# CTR-Lower-Main-Board-Rev-C-LED-5.net
KiCad netlist of a schematic drawn in Altium Designer
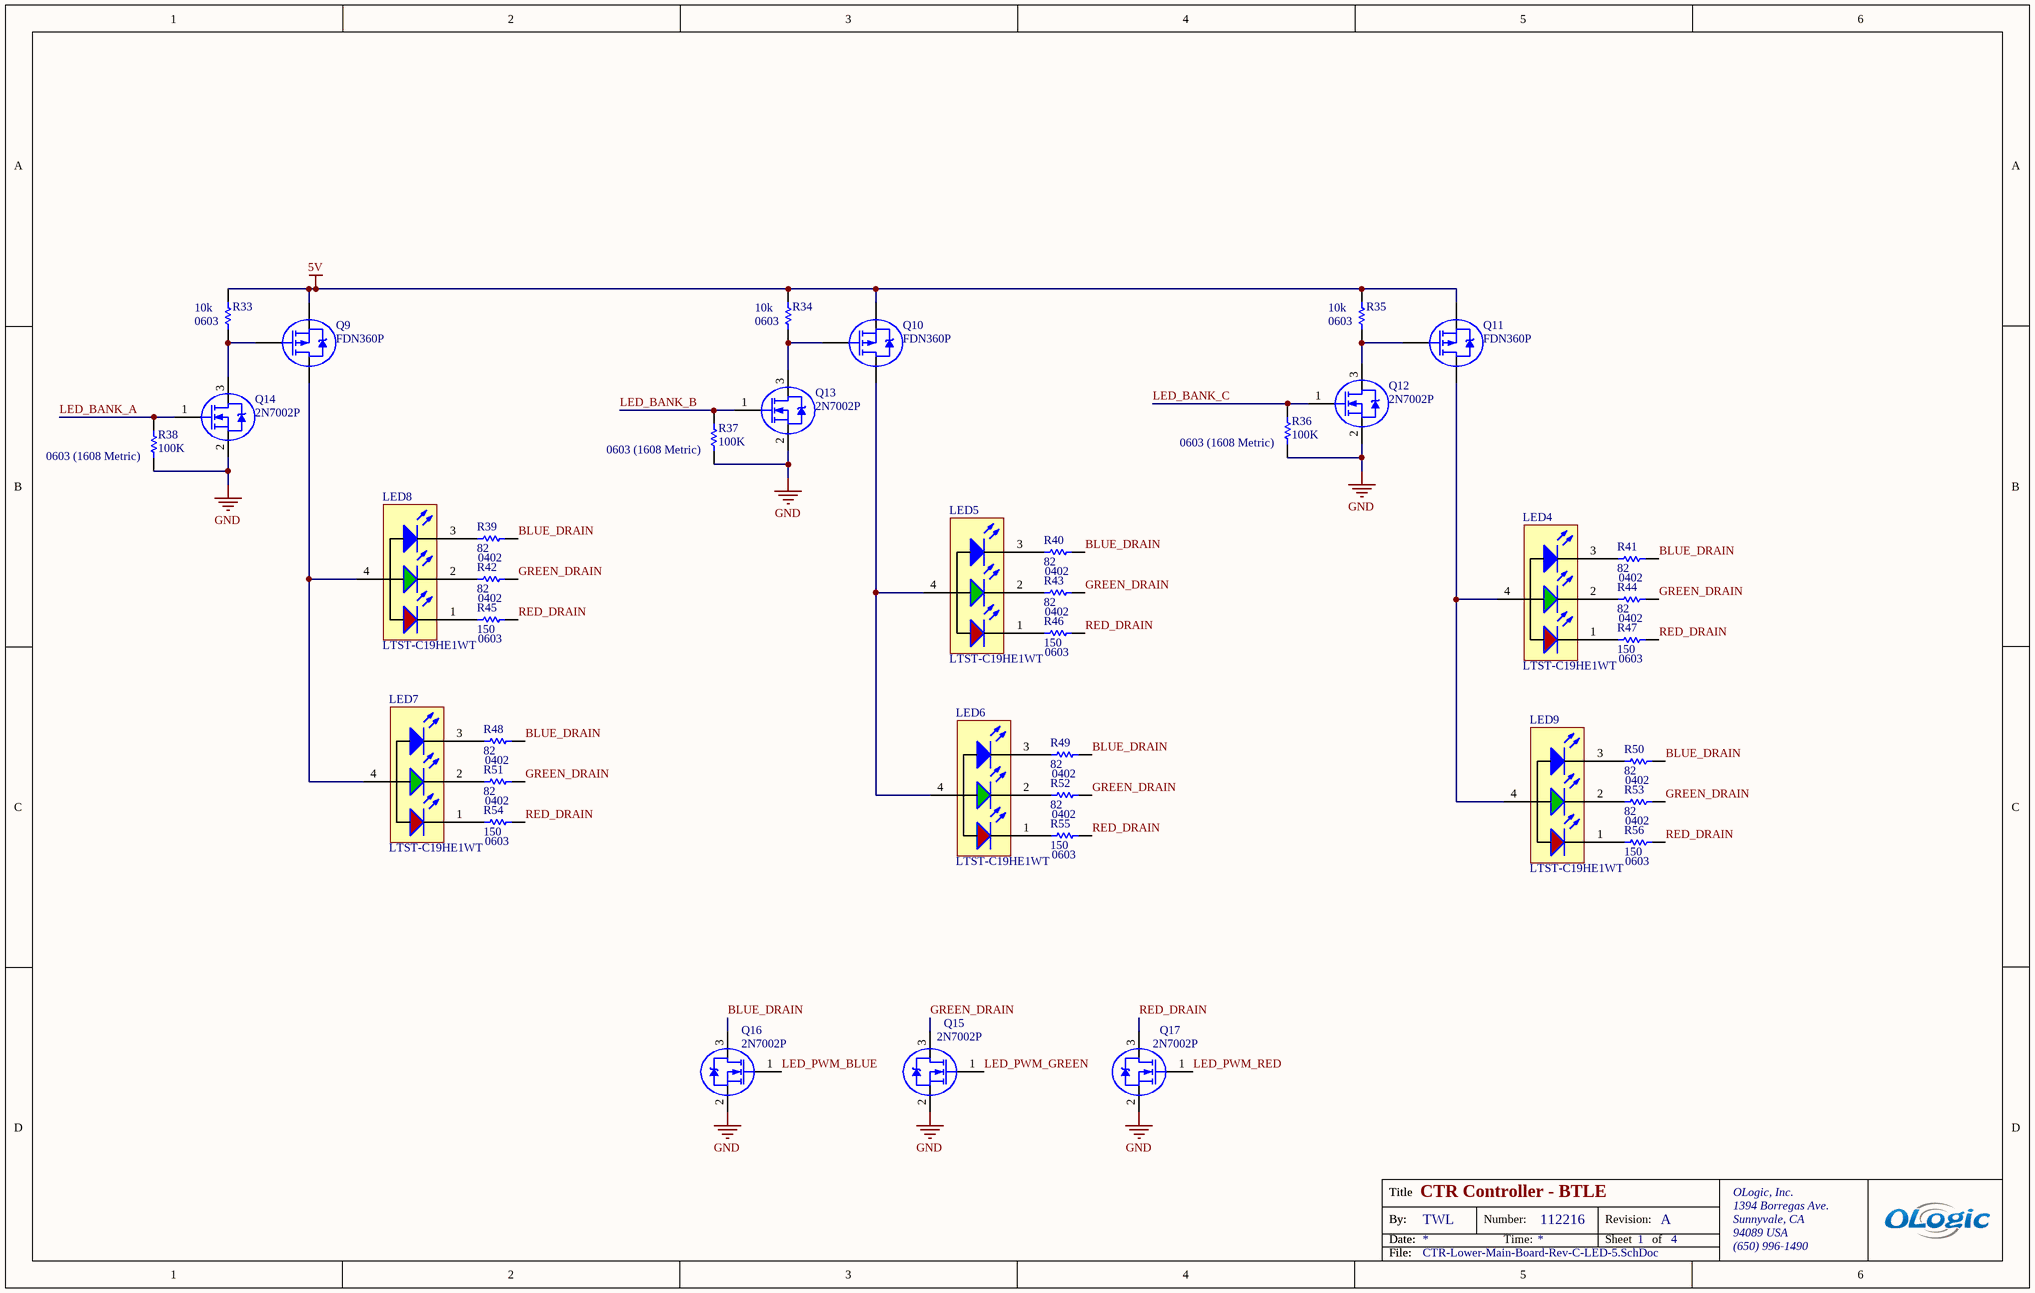
[diagram p0: CTR-Lower-Main-Board-Rev-C-LED-5.SchDoc]

(export (version "E")
  (design (tool "Eeschema 10.0.6"))
  (components
    (comp (ref "LED4")
      (value "Red, Green, Blue (RGB)")
      (footprint "LTST-C19HE1WT")
      (description "LED RGB 624/525/470NM DIFF SMD")
      (fields
        (field (name "MANUFACTURER") "Lite-On Inc.")
        (field (name "MANUFACTURER PART NUMBER") "LTST-C19HE1WT")
      )
      (libsource (lib "OLogic-Diode-Opto-LED") (part "LTST-C19HE1WT"))
    )
    (comp (ref "LED5")
      (value "Red, Green, Blue (RGB)")
      (footprint "LTST-C19HE1WT")
      (description "LED RGB 624/525/470NM DIFF SMD")
      (fields
        (field (name "MANUFACTURER") "Lite-On Inc.")
        (field (name "MANUFACTURER PART NUMBER") "LTST-C19HE1WT")
      )
      (libsource (lib "OLogic-Diode-Opto-LED") (part "LTST-C19HE1WT"))
    )
    (comp (ref "LED6")
      (value "Red, Green, Blue (RGB)")
      (footprint "LTST-C19HE1WT")
      (description "LED RGB 624/525/470NM DIFF SMD")
      (fields
        (field (name "MANUFACTURER") "Lite-On Inc.")
        (field (name "MANUFACTURER PART NUMBER") "LTST-C19HE1WT")
      )
      (libsource (lib "OLogic-Diode-Opto-LED") (part "LTST-C19HE1WT"))
    )
    (comp (ref "LED7")
      (value "Red, Green, Blue (RGB)")
      (footprint "LTST-C19HE1WT")
      (description "LED RGB 624/525/470NM DIFF SMD")
      (fields
        (field (name "MANUFACTURER") "Lite-On Inc.")
        (field (name "MANUFACTURER PART NUMBER") "LTST-C19HE1WT")
      )
      (libsource (lib "OLogic-Diode-Opto-LED") (part "LTST-C19HE1WT"))
    )
    (comp (ref "LED8")
      (value "Red, Green, Blue (RGB)")
      (footprint "LTST-C19HE1WT")
      (description "LED RGB 624/525/470NM DIFF SMD")
      (fields
        (field (name "MANUFACTURER") "Lite-On Inc.")
        (field (name "MANUFACTURER PART NUMBER") "LTST-C19HE1WT")
      )
      (libsource (lib "OLogic-Diode-Opto-LED") (part "LTST-C19HE1WT"))
    )
    (comp (ref "LED9")
      (value "Red, Green, Blue (RGB)")
      (footprint "LTST-C19HE1WT")
      (description "LED RGB 624/525/470NM DIFF SMD")
      (fields
        (field (name "MANUFACTURER") "Lite-On Inc.")
        (field (name "MANUFACTURER PART NUMBER") "LTST-C19HE1WT")
      )
      (libsource (lib "OLogic-Diode-Opto-LED") (part "LTST-C19HE1WT"))
    )
    (comp (ref "Q9")
      (value "FDN360P")
      (footprint "SOT23")
      (description "Single P-Channel MOSFET")
      (fields (field (name "MANUFACTURER") "Fairchild Semi"))
      (libsource (lib "OLogic-Trans-Drivers") (part "FDN360P"))
    )
    (comp (ref "Q10")
      (value "FDN360P")
      (footprint "SOT23")
      (description "Single P-Channel MOSFET")
      (fields (field (name "MANUFACTURER") "Fairchild Semi"))
      (libsource (lib "OLogic-Trans-Drivers") (part "FDN360P"))
    )
    (comp (ref "Q11")
      (value "FDN360P")
      (footprint "SOT23")
      (description "Single P-Channel MOSFET")
      (fields (field (name "MANUFACTURER") "Fairchild Semi"))
      (libsource (lib "OLogic-Trans-Drivers") (part "FDN360P"))
    )
    (comp (ref "Q12")
      (value "2N7002P")
      (footprint "SOT23")
      (description "MOSFET N-CH 60V 0.36A SOT-23")
      (fields
        (field (name "MANUFACTURER") "NXP Semiconductors")
        (field (name "MANUFACTURER PART NUMBER") "2N7002P,235")
      )
      (libsource (lib "OLogic-Trans-Drivers") (part "2N7002P"))
    )
    (comp (ref "Q13")
      (value "2N7002P")
      (footprint "SOT23")
      (description "MOSFET N-CH 60V 0.36A SOT-23")
      (fields
        (field (name "MANUFACTURER") "NXP Semiconductors")
        (field (name "MANUFACTURER PART NUMBER") "2N7002P,235")
      )
      (libsource (lib "OLogic-Trans-Drivers") (part "2N7002P"))
    )
    (comp (ref "Q14")
      (value "2N7002P")
      (footprint "SOT23")
      (description "MOSFET N-CH 60V 0.36A SOT-23")
      (fields
        (field (name "MANUFACTURER") "NXP Semiconductors")
        (field (name "MANUFACTURER PART NUMBER") "2N7002P,235")
      )
      (libsource (lib "OLogic-Trans-Drivers") (part "2N7002P"))
    )
    (comp (ref "Q15")
      (value "2N7002P")
      (footprint "SOT23")
      (description "MOSFET N-CH 60V 0.36A SOT-23")
      (fields
        (field (name "MANUFACTURER") "NXP Semiconductors")
        (field (name "MANUFACTURER PART NUMBER") "2N7002P,235")
      )
      (libsource (lib "") (part "2N7002P_1"))
    )
    (comp (ref "Q16")
      (value "2N7002P")
      (footprint "SOT23")
      (description "MOSFET N-CH 60V 0.36A SOT-23")
      (fields
        (field (name "MANUFACTURER") "NXP Semiconductors")
        (field (name "MANUFACTURER PART NUMBER") "2N7002P,235")
      )
      (libsource (lib "") (part "2N7002P_1"))
    )
    (comp (ref "Q17")
      (value "2N7002P")
      (footprint "SOT23")
      (description "MOSFET N-CH 60V 0.36A SOT-23")
      (fields
        (field (name "MANUFACTURER") "NXP Semiconductors")
        (field (name "MANUFACTURER PART NUMBER") "2N7002P,235")
      )
      (libsource (lib "") (part "2N7002P_1"))
    )
    (comp (ref "R33")
      (value "10K 1%")
      (footprint "RESC0603(1608)_N")
      (description "10K 0603")
      (fields
        (field (name "MANUFACTURER") "Panasonic Electronic Components")
        (field (name "MANUFACTURER PART NUMBER") "ERJ-3EKF1002V")
        (field (name "RESISTANCE (OHMS)") "10k")
        (field (name "SUPPLIER DEVICE PACKAGE") "0603")
      )
      (libsource (lib "OLogic-Passive") (part "RES 10K OHM 1/10W 1% 0603 SMD"))
    )
    (comp (ref "R34")
      (value "10K 1%")
      (footprint "RESC0603(1608)_N")
      (description "10K 0603")
      (fields
        (field (name "MANUFACTURER") "Panasonic Electronic Components")
        (field (name "MANUFACTURER PART NUMBER") "ERJ-3EKF1002V")
        (field (name "RESISTANCE (OHMS)") "10k")
        (field (name "SUPPLIER DEVICE PACKAGE") "0603")
      )
      (libsource (lib "OLogic-Passive") (part "RES 10K OHM 1/10W 1% 0603 SMD"))
    )
    (comp (ref "R35")
      (value "10K 1%")
      (footprint "RESC0603(1608)_N")
      (description "10K 0603")
      (fields
        (field (name "MANUFACTURER") "Panasonic Electronic Components")
        (field (name "MANUFACTURER PART NUMBER") "ERJ-3EKF1002V")
        (field (name "RESISTANCE (OHMS)") "10k")
        (field (name "SUPPLIER DEVICE PACKAGE") "0603")
      )
      (libsource (lib "OLogic-Passive") (part "RES 10K OHM 1/10W 1% 0603 SMD"))
    )
    (comp (ref "R36")
      (value "100K")
      (footprint "RESC0603(1608)_N")
      (description "100K 0603")
      (fields
        (field (name "MANUFACTURER") "Rohm Semiconductor")
        (field (name "MANUFACTURER PART NUMBER") "ESR03EZPJ104")
        (field (name "PACKAGE / CASE") "0603 (1608 Metric)")
      )
      (libsource (lib "OLogic-Passive") (part "RES 100K OHM 5% 1/4W 0603"))
    )
    (comp (ref "R37")
      (value "100K")
      (footprint "RESC0603(1608)_N")
      (description "100K 0603")
      (fields
        (field (name "MANUFACTURER") "Rohm Semiconductor")
        (field (name "MANUFACTURER PART NUMBER") "ESR03EZPJ104")
        (field (name "PACKAGE / CASE") "0603 (1608 Metric)")
      )
      (libsource (lib "OLogic-Passive") (part "RES 100K OHM 5% 1/4W 0603"))
    )
    (comp (ref "R38")
      (value "100K")
      (footprint "RESC0603(1608)_N")
      (description "100K 0603")
      (fields
        (field (name "MANUFACTURER") "Rohm Semiconductor")
        (field (name "MANUFACTURER PART NUMBER") "ESR03EZPJ104")
        (field (name "PACKAGE / CASE") "0603 (1608 Metric)")
      )
      (libsource (lib "OLogic-Passive") (part "RES 100K OHM 5% 1/4W 0603"))
    )
    (comp (ref "R39")
      (value "?")
      (footprint "RESC0402(1005)_N")
      (description "82 0402")
      (fields
        (field (name "MANUFACTURER") "Panasonic Electronic Components")
        (field (name "MANUFACTURER PART NUMBER") "ERJ-2RKF82R0X")
        (field (name "SUPPLIER DEVICE PACKAGE") "0402")
        (field (name "RESISTANCE (OHMS)") "82")
        (field (name "CREATOR") "osman")
      )
      (libsource (lib "OLogic-Passive") (part "RES 82 OHM 1% 1/10W 0402"))
    )
    (comp (ref "R40")
      (value "?")
      (footprint "RESC0402(1005)_N")
      (description "82 0402")
      (fields
        (field (name "MANUFACTURER") "Panasonic Electronic Components")
        (field (name "MANUFACTURER PART NUMBER") "ERJ-2RKF82R0X")
        (field (name "SUPPLIER DEVICE PACKAGE") "0402")
        (field (name "RESISTANCE (OHMS)") "82")
        (field (name "CREATOR") "osman")
      )
      (libsource (lib "OLogic-Passive") (part "RES 82 OHM 1% 1/10W 0402"))
    )
    (comp (ref "R41")
      (value "?")
      (footprint "RESC0402(1005)_N")
      (description "82 0402")
      (fields
        (field (name "MANUFACTURER") "Panasonic Electronic Components")
        (field (name "MANUFACTURER PART NUMBER") "ERJ-2RKF82R0X")
        (field (name "SUPPLIER DEVICE PACKAGE") "0402")
        (field (name "RESISTANCE (OHMS)") "82")
        (field (name "CREATOR") "osman")
      )
      (libsource (lib "OLogic-Passive") (part "RES 82 OHM 1% 1/10W 0402"))
    )
    (comp (ref "R42")
      (value "?")
      (footprint "RESC0402(1005)_N")
      (description "82 0402")
      (fields
        (field (name "MANUFACTURER") "Panasonic Electronic Components")
        (field (name "MANUFACTURER PART NUMBER") "ERJ-2RKF82R0X")
        (field (name "SUPPLIER DEVICE PACKAGE") "0402")
        (field (name "RESISTANCE (OHMS)") "82")
        (field (name "CREATOR") "osman")
      )
      (libsource (lib "OLogic-Passive") (part "RES 82 OHM 1% 1/10W 0402"))
    )
    (comp (ref "R43")
      (value "?")
      (footprint "RESC0402(1005)_N")
      (description "82 0402")
      (fields
        (field (name "MANUFACTURER") "Panasonic Electronic Components")
        (field (name "MANUFACTURER PART NUMBER") "ERJ-2RKF82R0X")
        (field (name "SUPPLIER DEVICE PACKAGE") "0402")
        (field (name "RESISTANCE (OHMS)") "82")
        (field (name "CREATOR") "osman")
      )
      (libsource (lib "OLogic-Passive") (part "RES 82 OHM 1% 1/10W 0402"))
    )
    (comp (ref "R44")
      (value "?")
      (footprint "RESC0402(1005)_N")
      (description "82 0402")
      (fields
        (field (name "MANUFACTURER") "Panasonic Electronic Components")
        (field (name "MANUFACTURER PART NUMBER") "ERJ-2RKF82R0X")
        (field (name "SUPPLIER DEVICE PACKAGE") "0402")
        (field (name "RESISTANCE (OHMS)") "82")
        (field (name "CREATOR") "osman")
      )
      (libsource (lib "OLogic-Passive") (part "RES 82 OHM 1% 1/10W 0402"))
    )
    (comp (ref "R45")
      (value "150")
      (footprint "RESC0603(1608)_N")
      (description "150 0603")
      (fields
        (field (name "MANUFACTURER") "Yageo")
        (field (name "MANUFACTURER PART NUMBER") "RC0603FR-07150RL")
        (field (name "SUPPLIER DEVICE PACKAGE") "0603")
      )
      (libsource (lib "OLogic-Passive") (part "RES 150 OHM 1/10W 1% 0603 SMD"))
    )
    (comp (ref "R46")
      (value "150")
      (footprint "RESC0603(1608)_N")
      (description "150 0603")
      (fields
        (field (name "MANUFACTURER") "Yageo")
        (field (name "MANUFACTURER PART NUMBER") "RC0603FR-07150RL")
        (field (name "SUPPLIER DEVICE PACKAGE") "0603")
      )
      (libsource (lib "OLogic-Passive") (part "RES 150 OHM 1/10W 1% 0603 SMD"))
    )
    (comp (ref "R47")
      (value "150")
      (footprint "RESC0603(1608)_N")
      (description "150 0603")
      (fields
        (field (name "MANUFACTURER") "Yageo")
        (field (name "MANUFACTURER PART NUMBER") "RC0603FR-07150RL")
        (field (name "SUPPLIER DEVICE PACKAGE") "0603")
      )
      (libsource (lib "OLogic-Passive") (part "RES 150 OHM 1/10W 1% 0603 SMD"))
    )
    (comp (ref "R48")
      (value "?")
      (footprint "RESC0402(1005)_N")
      (description "82 0402")
      (fields
        (field (name "MANUFACTURER") "Panasonic Electronic Components")
        (field (name "MANUFACTURER PART NUMBER") "ERJ-2RKF82R0X")
        (field (name "SUPPLIER DEVICE PACKAGE") "0402")
        (field (name "RESISTANCE (OHMS)") "82")
        (field (name "CREATOR") "osman")
      )
      (libsource (lib "OLogic-Passive") (part "RES 82 OHM 1% 1/10W 0402"))
    )
    (comp (ref "R49")
      (value "?")
      (footprint "RESC0402(1005)_N")
      (description "82 0402")
      (fields
        (field (name "MANUFACTURER") "Panasonic Electronic Components")
        (field (name "MANUFACTURER PART NUMBER") "ERJ-2RKF82R0X")
        (field (name "SUPPLIER DEVICE PACKAGE") "0402")
        (field (name "RESISTANCE (OHMS)") "82")
        (field (name "CREATOR") "osman")
      )
      (libsource (lib "OLogic-Passive") (part "RES 82 OHM 1% 1/10W 0402"))
    )
    (comp (ref "R50")
      (value "?")
      (footprint "RESC0402(1005)_N")
      (description "82 0402")
      (fields
        (field (name "MANUFACTURER") "Panasonic Electronic Components")
        (field (name "MANUFACTURER PART NUMBER") "ERJ-2RKF82R0X")
        (field (name "SUPPLIER DEVICE PACKAGE") "0402")
        (field (name "RESISTANCE (OHMS)") "82")
        (field (name "CREATOR") "osman")
      )
      (libsource (lib "OLogic-Passive") (part "RES 82 OHM 1% 1/10W 0402"))
    )
    (comp (ref "R51")
      (value "?")
      (footprint "RESC0402(1005)_N")
      (description "82 0402")
      (fields
        (field (name "MANUFACTURER") "Panasonic Electronic Components")
        (field (name "MANUFACTURER PART NUMBER") "ERJ-2RKF82R0X")
        (field (name "SUPPLIER DEVICE PACKAGE") "0402")
        (field (name "RESISTANCE (OHMS)") "82")
        (field (name "CREATOR") "osman")
      )
      (libsource (lib "OLogic-Passive") (part "RES 82 OHM 1% 1/10W 0402"))
    )
    (comp (ref "R52")
      (value "?")
      (footprint "RESC0402(1005)_N")
      (description "82 0402")
      (fields
        (field (name "MANUFACTURER") "Panasonic Electronic Components")
        (field (name "MANUFACTURER PART NUMBER") "ERJ-2RKF82R0X")
        (field (name "SUPPLIER DEVICE PACKAGE") "0402")
        (field (name "RESISTANCE (OHMS)") "82")
        (field (name "CREATOR") "osman")
      )
      (libsource (lib "OLogic-Passive") (part "RES 82 OHM 1% 1/10W 0402"))
    )
    (comp (ref "R53")
      (value "?")
      (footprint "RESC0402(1005)_N")
      (description "82 0402")
      (fields
        (field (name "MANUFACTURER") "Panasonic Electronic Components")
        (field (name "MANUFACTURER PART NUMBER") "ERJ-2RKF82R0X")
        (field (name "SUPPLIER DEVICE PACKAGE") "0402")
        (field (name "RESISTANCE (OHMS)") "82")
        (field (name "CREATOR") "osman")
      )
      (libsource (lib "OLogic-Passive") (part "RES 82 OHM 1% 1/10W 0402"))
    )
    (comp (ref "R54")
      (value "150")
      (footprint "RESC0603(1608)_N")
      (description "150 0603")
      (fields
        (field (name "MANUFACTURER") "Yageo")
        (field (name "MANUFACTURER PART NUMBER") "RC0603FR-07150RL")
        (field (name "SUPPLIER DEVICE PACKAGE") "0603")
      )
      (libsource (lib "OLogic-Passive") (part "RES 150 OHM 1/10W 1% 0603 SMD"))
    )
    (comp (ref "R55")
      (value "150")
      (footprint "RESC0603(1608)_N")
      (description "150 0603")
      (fields
        (field (name "MANUFACTURER") "Yageo")
        (field (name "MANUFACTURER PART NUMBER") "RC0603FR-07150RL")
        (field (name "SUPPLIER DEVICE PACKAGE") "0603")
      )
      (libsource (lib "OLogic-Passive") (part "RES 150 OHM 1/10W 1% 0603 SMD"))
    )
    (comp (ref "R56")
      (value "150")
      (footprint "RESC0603(1608)_N")
      (description "150 0603")
      (fields
        (field (name "MANUFACTURER") "Yageo")
        (field (name "MANUFACTURER PART NUMBER") "RC0603FR-07150RL")
        (field (name "SUPPLIER DEVICE PACKAGE") "0603")
      )
      (libsource (lib "OLogic-Passive") (part "RES 150 OHM 1/10W 1% 0603 SMD"))
    )
  )
  (nets
    (net (code "1") (name "/BLUE_DRAIN") (class "Default")
      (node (ref "Q16") (pin "3") (pinfunction "D_3") (pintype "power_in"))
      (node (ref "R39") (pin "1") (pinfunction "1_1") (pintype "passive"))
      (node (ref "R40") (pin "1") (pinfunction "1_1") (pintype "passive"))
      (node (ref "R41") (pin "1") (pinfunction "1_1") (pintype "passive"))
      (node (ref "R48") (pin "1") (pinfunction "1_1") (pintype "passive"))
      (node (ref "R49") (pin "1") (pinfunction "1_1") (pintype "passive"))
      (node (ref "R50") (pin "1") (pinfunction "1_1") (pintype "passive"))
    )
    (net (code "2") (name "/GREEN_DRAIN") (class "Default")
      (node (ref "Q15") (pin "3") (pinfunction "D_3") (pintype "power_in"))
      (node (ref "R42") (pin "1") (pinfunction "1_1") (pintype "passive"))
      (node (ref "R43") (pin "1") (pinfunction "1_1") (pintype "passive"))
      (node (ref "R44") (pin "1") (pinfunction "1_1") (pintype "passive"))
      (node (ref "R51") (pin "1") (pinfunction "1_1") (pintype "passive"))
      (node (ref "R52") (pin "1") (pinfunction "1_1") (pintype "passive"))
      (node (ref "R53") (pin "1") (pinfunction "1_1") (pintype "passive"))
    )
    (net (code "3") (name "/LED_BANK_A") (class "Default")
      (node (ref "Q14") (pin "1") (pinfunction "G_1") (pintype "passive"))
      (node (ref "R38") (pin "2") (pinfunction "2_2") (pintype "passive"))
    )
    (net (code "4") (name "/LED_BANK_B") (class "Default")
      (node (ref "Q13") (pin "1") (pinfunction "G_1") (pintype "passive"))
      (node (ref "R37") (pin "2") (pinfunction "2_2") (pintype "passive"))
    )
    (net (code "5") (name "/LED_BANK_C") (class "Default")
      (node (ref "Q12") (pin "1") (pinfunction "G_1") (pintype "passive"))
      (node (ref "R36") (pin "2") (pinfunction "2_2") (pintype "passive"))
    )
    (net (code "6") (name "/LED_PWM_BLUE") (class "Default")
      (node (ref "Q16") (pin "1") (pinfunction "G_1") (pintype "passive"))
    )
    (net (code "7") (name "/LED_PWM_GREEN") (class "Default")
      (node (ref "Q15") (pin "1") (pinfunction "G_1") (pintype "passive"))
    )
    (net (code "8") (name "/LED_PWM_RED") (class "Default")
      (node (ref "Q17") (pin "1") (pinfunction "G_1") (pintype "passive"))
    )
    (net (code "9") (name "/RED_DRAIN") (class "Default")
      (node (ref "Q17") (pin "3") (pinfunction "D_3") (pintype "power_in"))
      (node (ref "R45") (pin "1") (pinfunction "1_1") (pintype "passive"))
      (node (ref "R46") (pin "1") (pinfunction "1_1") (pintype "passive"))
      (node (ref "R47") (pin "1") (pinfunction "1_1") (pintype "passive"))
      (node (ref "R54") (pin "1") (pinfunction "1_1") (pintype "passive"))
      (node (ref "R55") (pin "1") (pinfunction "1_1") (pintype "passive"))
      (node (ref "R56") (pin "1") (pinfunction "1_1") (pintype "passive"))
    )
    (net (code "10") (name "5V") (class "Default")
      (node (ref "Q10") (pin "2") (pinfunction "S_2") (pintype "passive"))
      (node (ref "Q11") (pin "2") (pinfunction "S_2") (pintype "passive"))
      (node (ref "Q9") (pin "2") (pinfunction "S_2") (pintype "passive"))
      (node (ref "R33") (pin "2") (pinfunction "2_2") (pintype "passive"))
      (node (ref "R34") (pin "2") (pinfunction "2_2") (pintype "passive"))
      (node (ref "R35") (pin "2") (pinfunction "2_2") (pintype "passive"))
    )
    (net (code "11") (name "GND") (class "Default")
      (node (ref "Q12") (pin "2") (pinfunction "S_2") (pintype "passive"))
      (node (ref "Q13") (pin "2") (pinfunction "S_2") (pintype "passive"))
      (node (ref "Q14") (pin "2") (pinfunction "S_2") (pintype "passive"))
      (node (ref "Q15") (pin "2") (pinfunction "S_2") (pintype "passive"))
      (node (ref "Q16") (pin "2") (pinfunction "S_2") (pintype "passive"))
      (node (ref "Q17") (pin "2") (pinfunction "S_2") (pintype "passive"))
      (node (ref "R36") (pin "1") (pinfunction "1_1") (pintype "passive"))
      (node (ref "R37") (pin "1") (pinfunction "1_1") (pintype "passive"))
      (node (ref "R38") (pin "1") (pinfunction "1_1") (pintype "passive"))
    )
    (net (code "12") (name "Net-(LED4-Anode)") (class "Default")
      (node (ref "LED4") (pin "4") (pinfunction "Anode_4") (pintype "passive"))
      (node (ref "LED9") (pin "4") (pinfunction "Anode_4") (pintype "passive"))
      (node (ref "Q11") (pin "3") (pinfunction "D_3") (pintype "passive"))
    )
    (net (code "13") (name "Net-(LED4-B)") (class "Default")
      (node (ref "LED4") (pin "3") (pinfunction "B_3") (pintype "passive"))
      (node (ref "R41") (pin "2") (pinfunction "2_2") (pintype "passive"))
    )
    (net (code "14") (name "Net-(LED4-G)") (class "Default")
      (node (ref "LED4") (pin "2") (pinfunction "G_2") (pintype "passive"))
      (node (ref "R44") (pin "2") (pinfunction "2_2") (pintype "passive"))
    )
    (net (code "15") (name "Net-(LED4-R)") (class "Default")
      (node (ref "LED4") (pin "1") (pinfunction "R_1") (pintype "passive"))
      (node (ref "R47") (pin "2") (pinfunction "2_2") (pintype "passive"))
    )
    (net (code "16") (name "Net-(LED5-Anode)") (class "Default")
      (node (ref "LED5") (pin "4") (pinfunction "Anode_4") (pintype "passive"))
      (node (ref "LED6") (pin "4") (pinfunction "Anode_4") (pintype "passive"))
      (node (ref "Q10") (pin "3") (pinfunction "D_3") (pintype "passive"))
    )
    (net (code "17") (name "Net-(LED5-B)") (class "Default")
      (node (ref "LED5") (pin "3") (pinfunction "B_3") (pintype "passive"))
      (node (ref "R40") (pin "2") (pinfunction "2_2") (pintype "passive"))
    )
    (net (code "18") (name "Net-(LED5-G)") (class "Default")
      (node (ref "LED5") (pin "2") (pinfunction "G_2") (pintype "passive"))
      (node (ref "R43") (pin "2") (pinfunction "2_2") (pintype "passive"))
    )
    (net (code "19") (name "Net-(LED5-R)") (class "Default")
      (node (ref "LED5") (pin "1") (pinfunction "R_1") (pintype "passive"))
      (node (ref "R46") (pin "2") (pinfunction "2_2") (pintype "passive"))
    )
    (net (code "20") (name "Net-(LED6-B)") (class "Default")
      (node (ref "LED6") (pin "3") (pinfunction "B_3") (pintype "passive"))
      (node (ref "R49") (pin "2") (pinfunction "2_2") (pintype "passive"))
    )
    (net (code "21") (name "Net-(LED6-G)") (class "Default")
      (node (ref "LED6") (pin "2") (pinfunction "G_2") (pintype "passive"))
      (node (ref "R52") (pin "2") (pinfunction "2_2") (pintype "passive"))
    )
    (net (code "22") (name "Net-(LED6-R)") (class "Default")
      (node (ref "LED6") (pin "1") (pinfunction "R_1") (pintype "passive"))
      (node (ref "R55") (pin "2") (pinfunction "2_2") (pintype "passive"))
    )
    (net (code "23") (name "Net-(LED7-Anode)") (class "Default")
      (node (ref "LED7") (pin "4") (pinfunction "Anode_4") (pintype "passive"))
      (node (ref "LED8") (pin "4") (pinfunction "Anode_4") (pintype "passive"))
      (node (ref "Q9") (pin "3") (pinfunction "D_3") (pintype "passive"))
    )
    (net (code "24") (name "Net-(LED7-B)") (class "Default")
      (node (ref "LED7") (pin "3") (pinfunction "B_3") (pintype "passive"))
      (node (ref "R48") (pin "2") (pinfunction "2_2") (pintype "passive"))
    )
    (net (code "25") (name "Net-(LED7-G)") (class "Default")
      (node (ref "LED7") (pin "2") (pinfunction "G_2") (pintype "passive"))
      (node (ref "R51") (pin "2") (pinfunction "2_2") (pintype "passive"))
    )
    (net (code "26") (name "Net-(LED7-R)") (class "Default")
      (node (ref "LED7") (pin "1") (pinfunction "R_1") (pintype "passive"))
      (node (ref "R54") (pin "2") (pinfunction "2_2") (pintype "passive"))
    )
    (net (code "27") (name "Net-(LED8-B)") (class "Default")
      (node (ref "LED8") (pin "3") (pinfunction "B_3") (pintype "passive"))
      (node (ref "R39") (pin "2") (pinfunction "2_2") (pintype "passive"))
    )
    (net (code "28") (name "Net-(LED8-G)") (class "Default")
      (node (ref "LED8") (pin "2") (pinfunction "G_2") (pintype "passive"))
      (node (ref "R42") (pin "2") (pinfunction "2_2") (pintype "passive"))
    )
    (net (code "29") (name "Net-(LED8-R)") (class "Default")
      (node (ref "LED8") (pin "1") (pinfunction "R_1") (pintype "passive"))
      (node (ref "R45") (pin "2") (pinfunction "2_2") (pintype "passive"))
    )
    (net (code "30") (name "Net-(LED9-B)") (class "Default")
      (node (ref "LED9") (pin "3") (pinfunction "B_3") (pintype "passive"))
      (node (ref "R50") (pin "2") (pinfunction "2_2") (pintype "passive"))
    )
    (net (code "31") (name "Net-(LED9-G)") (class "Default")
      (node (ref "LED9") (pin "2") (pinfunction "G_2") (pintype "passive"))
      (node (ref "R53") (pin "2") (pinfunction "2_2") (pintype "passive"))
    )
    (net (code "32") (name "Net-(LED9-R)") (class "Default")
      (node (ref "LED9") (pin "1") (pinfunction "R_1") (pintype "passive"))
      (node (ref "R56") (pin "2") (pinfunction "2_2") (pintype "passive"))
    )
    (net (code "33") (name "Net-(Q10-G)") (class "Default")
      (node (ref "Q10") (pin "1") (pinfunction "G_1") (pintype "passive"))
      (node (ref "Q13") (pin "3") (pinfunction "D_3") (pintype "power_in"))
      (node (ref "R34") (pin "1") (pinfunction "1_1") (pintype "passive"))
    )
    (net (code "34") (name "Net-(Q11-G)") (class "Default")
      (node (ref "Q11") (pin "1") (pinfunction "G_1") (pintype "passive"))
      (node (ref "Q12") (pin "3") (pinfunction "D_3") (pintype "power_in"))
      (node (ref "R35") (pin "1") (pinfunction "1_1") (pintype "passive"))
    )
    (net (code "35") (name "Net-(Q14-D)") (class "Default")
      (node (ref "Q14") (pin "3") (pinfunction "D_3") (pintype "power_in"))
      (node (ref "Q9") (pin "1") (pinfunction "G_1") (pintype "passive"))
      (node (ref "R33") (pin "1") (pinfunction "1_1") (pintype "passive"))
    )
  )
)
